# Sheet3.net
KiCad netlist of a schematic drawn in Altium Designer
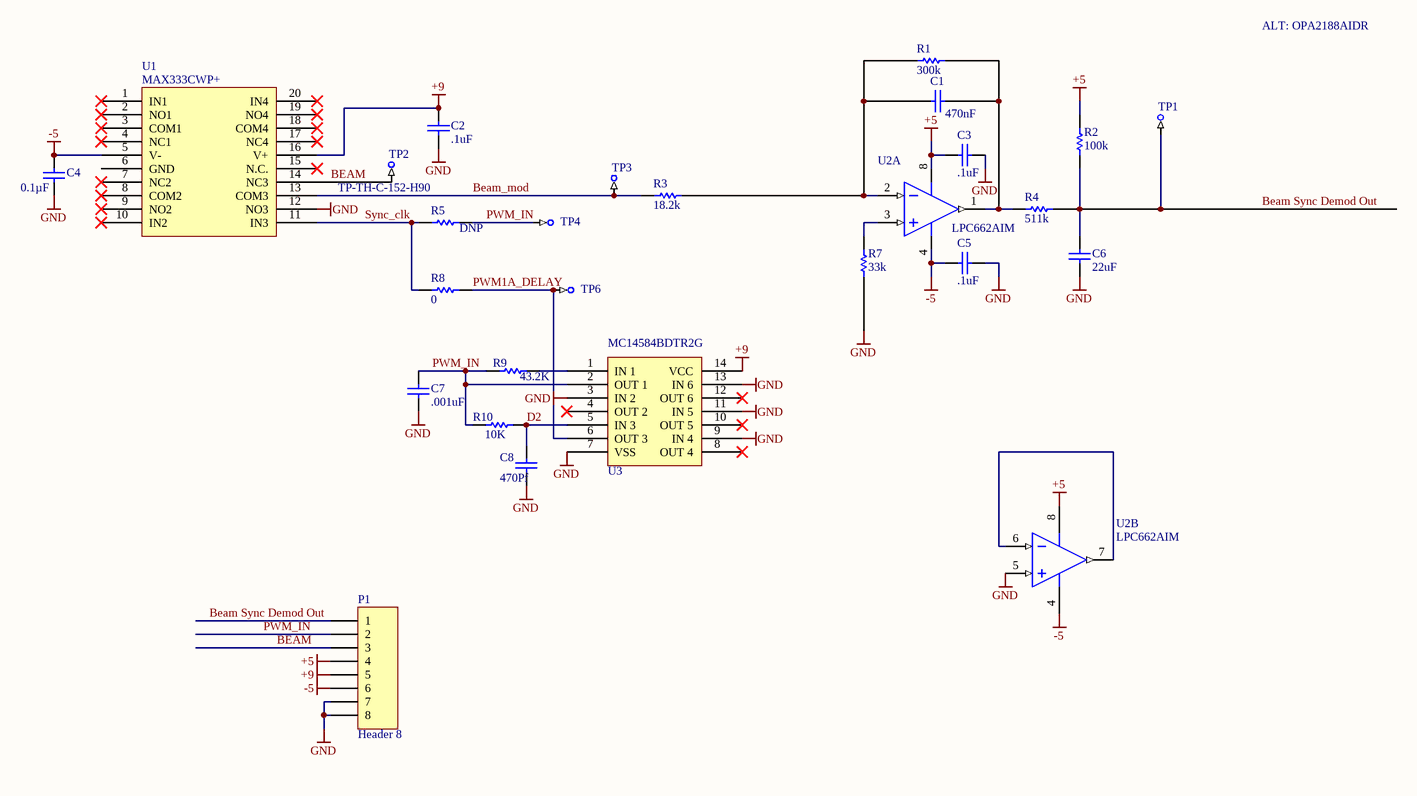
[diagram p0: Sheet3.SchDoc]

(export (version "E")
  (design (tool "Eeschema 10.0.6"))
  (components
    (comp (ref "C1")
      (value "470nF")
      (footprint "CAPC0805(2012)75_L")
      (description "CAP 150pF 16V ±10% 0805 (2012 Metric) Thickness 0.75mm SMD")
      (fields (field (name "TOLERANCE") "Â±10%"))
      (libsource (lib "Altium Content Vault") (part "CMP-1036-02117-1"))
    )
    (comp (ref "C2")
      (value ".1uF")
      (footprint "CAPC0805(2012)75_L")
      (description "CAP 150pF 16V ±10% 0805 (2012 Metric) Thickness 0.75mm SMD")
      (fields (field (name "TOLERANCE") "Â±10%"))
      (libsource (lib "Altium Content Vault") (part "CMP-1036-02117-1"))
    )
    (comp (ref "C3")
      (value ".1uF")
      (footprint "CAPC0805(2012)75_L")
      (description "CAP 150pF 16V ±10% 0805 (2012 Metric) Thickness 0.75mm SMD")
      (fields (field (name "TOLERANCE") "Â±10%"))
      (libsource (lib "Altium Content Vault") (part "CMP-1036-02117-1"))
    )
    (comp (ref "C4")
      (value "CAP CER 0.1UF 25V X7R 0805")
      (footprint "CAPC0805(2012)145_N")
      (fields
        (field (name "MANUFACTURER") "Murata Electronics North America")
        (field (name "MANUFACTURER PART NUMBER") "GRM21BR71E104KA01L")
        (field (name "CAPACITANCE") "0.1µF")
        (field (name "TOLERANCE") "±10%")
      )
      (libsource (lib "Altium Content Vault") (part "CMP-1036-04795-1"))
    )
    (comp (ref "C5")
      (value ".1uF")
      (footprint "CAPC0805(2012)75_L")
      (description "CAP 150pF 16V ±10% 0805 (2012 Metric) Thickness 0.75mm SMD")
      (fields (field (name "TOLERANCE") "Â±10%"))
      (libsource (lib "Altium Content Vault") (part "CMP-1036-02117-1"))
    )
    (comp (ref "C6")
      (value "22uF")
      (footprint "CAPC0805(2012)75_L")
      (description "CAP 150pF 16V ±10% 0805 (2012 Metric) Thickness 0.75mm SMD")
      (fields (field (name "TOLERANCE") "Â±10%"))
      (libsource (lib "Altium Content Vault") (part "CMP-1036-02117-1"))
    )
    (comp (ref "C7")
      (value ".001uF")
      (footprint "CAPC0805(2012)75_L")
      (description "CAP 150pF 16V ±10% 0805 (2012 Metric) Thickness 0.75mm SMD")
      (fields (field (name "TOLERANCE") "Â±10%"))
      (libsource (lib "Altium Content Vault") (part "CMP-1036-02117-1"))
    )
    (comp (ref "C8")
      (value "470Pf")
      (footprint "CAPC0805(2012)75_L")
      (description "CAP 150pF 16V ±10% 0805 (2012 Metric) Thickness 0.75mm SMD")
      (fields (field (name "TOLERANCE") "Â±10%"))
      (libsource (lib "Altium Content Vault") (part "CMP-1036-02117-1"))
    )
    (comp (ref "P1")
      (value "Header 8")
      (footprint "HDR1X8")
      (description "Header, 8-Pin")
      (fields (field (name "PUBLISHER") "Altium Limited"))
      (libsource (lib "Miscellaneous Connectors") (part "Header 8"))
    )
    (comp (ref "R1")
      (value "300k")
      (footprint "RESC0805(2012)_L")
      (description "2R55 0.125W 1% 0805 (2012 Metric)  SMD")
      (fields (field (name "TOLERANCE") "1 %") (field (name "POWER") "0.125 W"))
      (libsource (lib "Altium Content Vault") (part "CMP-1013-00215-1"))
    )
    (comp (ref "R2")
      (value "100k")
      (footprint "RESC0805(2012)_L")
      (description "2R55 0.125W 1% 0805 (2012 Metric)  SMD")
      (fields (field (name "TOLERANCE") "1 %") (field (name "POWER") "0.125 W"))
      (libsource (lib "Altium Content Vault") (part "CMP-1013-00215-1"))
    )
    (comp (ref "R3")
      (value "18.2k")
      (footprint "RESC0805(2012)_L")
      (description "2R55 0.125W 1% 0805 (2012 Metric)  SMD")
      (fields (field (name "TOLERANCE") "1 %") (field (name "POWER") "0.125 W"))
      (libsource (lib "Altium Content Vault") (part "CMP-1013-00215-1"))
    )
    (comp (ref "R4")
      (value "511k")
      (footprint "RESC0805(2012)_L")
      (description "2R55 0.125W 1% 0805 (2012 Metric)  SMD")
      (fields (field (name "TOLERANCE") "1 %") (field (name "POWER") "0.125 W"))
      (libsource (lib "Altium Content Vault") (part "CMP-1013-00215-1"))
    )
    (comp (ref "R5")
      (value "DNP")
      (footprint "RESC0805(2012)_L")
      (description "2R55 0.125W 1% 0805 (2012 Metric)  SMD")
      (fields (field (name "TOLERANCE") "1 %") (field (name "POWER") "0.125 W"))
      (libsource (lib "Altium Content Vault") (part "CMP-1013-00215-1"))
    )
    (comp (ref "R7")
      (value "33k")
      (footprint "RESC0805(2012)_L")
      (description "2R55 0.125W 1% 0805 (2012 Metric)  SMD")
      (fields (field (name "TOLERANCE") "1 %") (field (name "POWER") "0.125 W"))
      (libsource (lib "Altium Content Vault") (part "CMP-1013-00215-1"))
    )
    (comp (ref "R8")
      (value "0")
      (footprint "RESC0805(2012)_L")
      (description "2R55 0.125W 1% 0805 (2012 Metric)  SMD")
      (fields (field (name "TOLERANCE") "1 %") (field (name "POWER") "0.125 W"))
      (libsource (lib "Altium Content Vault") (part "CMP-1013-00215-1"))
    )
    (comp (ref "R9")
      (value "43.2K")
      (footprint "RESC0805(2012)_L")
      (description "2R55 0.125W 1% 0805 (2012 Metric)  SMD")
      (fields (field (name "TOLERANCE") "1 %") (field (name "POWER") "0.125 W"))
      (libsource (lib "Altium Content Vault") (part "CMP-1013-00215-1"))
    )
    (comp (ref "R10")
      (value "10K")
      (footprint "RESC0805(2012)_L")
      (description "2R55 0.125W 1% 0805 (2012 Metric)  SMD")
      (fields (field (name "TOLERANCE") "1 %") (field (name "POWER") "0.125 W"))
      (libsource (lib "Altium Content Vault") (part "CMP-1013-00215-1"))
    )
    (comp (ref "TP1")
      (value "TP-TH-C-152-H90")
      (footprint "TP-TH-C-152-H90")
      (description "Test Point, Through Hole, Hole Size 0.9 mm, PCB Mount with Silkscreen Box")
      (fields (field (name "MANUFACTURER") "No Vendor"))
      (libsource (lib "Altium Content Vault") (part "CMP-0484-00003-2"))
    )
    (comp (ref "TP2")
      (value "TP-TH-C-152-H90")
      (footprint "TP-TH-C-152-H90")
      (description "Test Point, Through Hole, Hole Size 0.9 mm, PCB Mount with Silkscreen Box")
      (fields (field (name "MANUFACTURER") "No Vendor"))
      (libsource (lib "Altium Content Vault") (part "TP-TH"))
    )
    (comp (ref "TP3")
      (value "TP-TH-C-152-H90")
      (footprint "TP-TH-C-152-H90")
      (description "Test Point, Through Hole, Hole Size 0.9 mm, PCB Mount with Silkscreen Box")
      (fields (field (name "MANUFACTURER") "No Vendor"))
      (libsource (lib "Altium Content Vault") (part "CMP-0484-00003-2"))
    )
    (comp (ref "TP4")
      (value "TP-TH-C-152-H90")
      (footprint "TP-TH-C-152-H90")
      (description "Test Point, Through Hole, Hole Size 0.9 mm, PCB Mount with Silkscreen Box")
      (fields (field (name "MANUFACTURER") "No Vendor"))
      (libsource (lib "Altium Content Vault") (part "CMP-0484-00003-2"))
    )
    (comp (ref "TP6")
      (value "TP-TH-C-152-H90")
      (footprint "TP-TH-C-152-H90")
      (description "Test Point, Through Hole, Hole Size 0.9 mm, PCB Mount with Silkscreen Box")
      (fields (field (name "MANUFACTURER") "No Vendor"))
      (libsource (lib "Altium Content Vault") (part "CMP-0484-00003-2"))
    )
    (comp (ref "U1")
      (value "MAX333CWP+")
      (footprint "TSOP65P640X90-20N")
      (description "IC SWITCH QUAD SPDT 20TSSOP")
      (fields (field (name "MANUFACTURER") "Maxim") (field (name "MANUFACTURER PART NUMBER") "MAX333AEUP+"))
      (libsource (lib "ZLS_Schematic_lib") (part "MAX333CWP+"))
    )
    (comp (ref "U2")
      (value "LPC662AIM")
      (footprint "D0008A_L")
      (description "Low Power CMOS Dual Operational Amplifier, 8-pin Narrow SOIC")
      (fields (field (name "MANUFACTURER") "Texas Instruments"))
      (libsource (lib "Altium Content Vault") (part "AMP-OPA-LM6132-8"))
    )
    (comp (ref "U3")
      (value "MC14584BDTR2G")
      (footprint "MC14584BDTR2G")
      (fields (field (name "MANUFACTURER") "ON Semiconductor") (field (name "BASE PART NUMBER") "4584"))
      (libsource (lib "ZLS_Schematic_lib") (part "MC14584BDTR2G"))
    )
  )
  (nets
    (net (code "1") (name "+5") (class "Default")
      (node (ref "C3") (pin "1") (pinfunction "1_1") (pintype "passive"))
      (node (ref "P1") (pin "4") (pinfunction "4_4") (pintype "passive"))
      (node (ref "R2") (pin "2") (pinfunction "2_2") (pintype "passive"))
      (node (ref "U2") (pin "8") (pinfunction "V+_8") (pintype "power_in"))
    )
    (net (code "2") (name "+9") (class "Default")
      (node (ref "C2") (pin "2") (pinfunction "2_2") (pintype "passive"))
      (node (ref "P1") (pin "5") (pinfunction "5_5") (pintype "passive"))
      (node (ref "U1") (pin "16") (pinfunction "V+_16") (pintype "power_in"))
      (node (ref "U3") (pin "14") (pinfunction "VCC_14") (pintype "passive"))
    )
    (net (code "3") (name "-5") (class "Default")
      (node (ref "C4") (pin "1") (pinfunction "1_1") (pintype "passive"))
      (node (ref "C5") (pin "1") (pinfunction "1_1") (pintype "passive"))
      (node (ref "P1") (pin "6") (pinfunction "6_6") (pintype "passive"))
      (node (ref "U1") (pin "5") (pinfunction "V-_5") (pintype "power_in"))
      (node (ref "U2") (pin "4") (pinfunction "V-_4") (pintype "power_in"))
    )
    (net (code "4") (name "/BEAM") (class "Default")
      (node (ref "P1") (pin "3") (pinfunction "3_3") (pintype "passive"))
      (node (ref "TP2") (pin "1") (pinfunction "1_1") (pintype "input"))
      (node (ref "U1") (pin "14") (pinfunction "NC3_14") (pintype "passive"))
    )
    (net (code "5") (name "/Beam Sync Demod Out") (class "Default")
      (node (ref "C6") (pin "2") (pinfunction "2_2") (pintype "passive"))
      (node (ref "P1") (pin "1") (pinfunction "1_1") (pintype "passive"))
      (node (ref "R2") (pin "1") (pinfunction "1_1") (pintype "passive"))
      (node (ref "R4") (pin "1") (pinfunction "1_1") (pintype "passive"))
      (node (ref "TP1") (pin "1") (pinfunction "1_1") (pintype "input"))
    )
    (net (code "6") (name "/Beam_mod") (class "Default")
      (node (ref "R3") (pin "2") (pinfunction "2_2") (pintype "passive"))
      (node (ref "TP3") (pin "1") (pinfunction "1_1") (pintype "input"))
      (node (ref "U1") (pin "13") (pinfunction "COM3_13") (pintype "passive"))
    )
    (net (code "7") (name "/D2") (class "Default")
      (node (ref "C8") (pin "2") (pinfunction "2_2") (pintype "passive"))
      (node (ref "R10") (pin "1") (pinfunction "1_1") (pintype "passive"))
      (node (ref "U3") (pin "5") (pinfunction "IN_3_5") (pintype "passive"))
    )
    (net (code "8") (name "/PWM1A_DELAY") (class "Default")
      (node (ref "R8") (pin "1") (pinfunction "1_1") (pintype "passive"))
      (node (ref "TP6") (pin "1") (pinfunction "1_1") (pintype "input"))
      (node (ref "U3") (pin "6") (pinfunction "OUT_3_6") (pintype "passive"))
    )
    (net (code "9") (name "/PWM_IN") (class "Default")
      (node (ref "C7") (pin "2") (pinfunction "2_2") (pintype "passive"))
      (node (ref "P1") (pin "2") (pinfunction "2_2") (pintype "passive"))
      (node (ref "R10") (pin "2") (pinfunction "2_2") (pintype "passive"))
      (node (ref "R5") (pin "1") (pinfunction "1_1") (pintype "passive"))
      (node (ref "R9") (pin "2") (pinfunction "2_2") (pintype "passive"))
      (node (ref "TP4") (pin "1") (pinfunction "1_1") (pintype "input"))
      (node (ref "U3") (pin "2") (pinfunction "OUT_1_2") (pintype "passive"))
    )
    (net (code "10") (name "/Sync_clk") (class "Default")
      (node (ref "R5") (pin "2") (pinfunction "2_2") (pintype "passive"))
      (node (ref "R8") (pin "2") (pinfunction "2_2") (pintype "passive"))
      (node (ref "U1") (pin "11") (pinfunction "IN3_11") (pintype "passive"))
    )
    (net (code "11") (name "GND") (class "Default")
      (node (ref "C2") (pin "1") (pinfunction "1_1") (pintype "passive"))
      (node (ref "C3") (pin "2") (pinfunction "2_2") (pintype "passive"))
      (node (ref "C4") (pin "2") (pinfunction "2_2") (pintype "passive"))
      (node (ref "C5") (pin "2") (pinfunction "2_2") (pintype "passive"))
      (node (ref "C6") (pin "1") (pinfunction "1_1") (pintype "passive"))
      (node (ref "C7") (pin "1") (pinfunction "1_1") (pintype "passive"))
      (node (ref "C8") (pin "1") (pinfunction "1_1") (pintype "passive"))
      (node (ref "P1") (pin "7") (pinfunction "7_7") (pintype "passive"))
      (node (ref "P1") (pin "8") (pinfunction "8_8") (pintype "passive"))
      (node (ref "R7") (pin "1") (pinfunction "1_1") (pintype "passive"))
      (node (ref "U1") (pin "12") (pinfunction "NO3_12") (pintype "passive"))
      (node (ref "U2") (pin "5") (pinfunction "INB+_5") (pintype "input"))
      (node (ref "U3") (pin "11") (pinfunction "IN_5_11") (pintype "passive"))
      (node (ref "U3") (pin "13") (pinfunction "IN_6_13") (pintype "passive"))
      (node (ref "U3") (pin "3") (pinfunction "IN_2_3") (pintype "passive"))
      (node (ref "U3") (pin "7") (pinfunction "VSS_7") (pintype "passive"))
      (node (ref "U3") (pin "9") (pinfunction "IN_4_9") (pintype "passive"))
    )
    (net (code "12") (name "Net-(U2A-INA+)") (class "Default")
      (node (ref "R7") (pin "2") (pinfunction "2_2") (pintype "passive"))
      (node (ref "U2") (pin "3") (pinfunction "INA+_3") (pintype "input"))
    )
    (net (code "13") (name "Net-(U2A-INA-)") (class "Default")
      (node (ref "C1") (pin "1") (pinfunction "1_1") (pintype "passive"))
      (node (ref "R1") (pin "2") (pinfunction "2_2") (pintype "passive"))
      (node (ref "R3") (pin "1") (pinfunction "1_1") (pintype "passive"))
      (node (ref "U2") (pin "2") (pinfunction "INA-_2") (pintype "input"))
    )
    (net (code "14") (name "Net-(U2A-OUTA)") (class "Default")
      (node (ref "C1") (pin "2") (pinfunction "2_2") (pintype "passive"))
      (node (ref "R1") (pin "1") (pinfunction "1_1") (pintype "passive"))
      (node (ref "R4") (pin "2") (pinfunction "2_2") (pintype "passive"))
      (node (ref "U2") (pin "1") (pinfunction "OUTA_1") (pintype "output"))
    )
    (net (code "15") (name "Net-(U2B-INB-)") (class "Default")
      (node (ref "U2") (pin "6") (pinfunction "INB-_6") (pintype "input"))
      (node (ref "U2") (pin "7") (pinfunction "OUTB_7") (pintype "output"))
    )
    (net (code "16") (name "Net-(U3-IN_1)") (class "Default")
      (node (ref "R9") (pin "1") (pinfunction "1_1") (pintype "passive"))
      (node (ref "U3") (pin "1") (pinfunction "IN_1_1") (pintype "passive"))
    )
    (net (code "17") (name "unconnected-(U1-COM1-Pad3)") (class "Default")
      (node (ref "U1") (pin "3") (pinfunction "COM1_3") (pintype "passive+no_connect"))
    )
    (net (code "18") (name "unconnected-(U1-COM2-Pad8)") (class "Default")
      (node (ref "U1") (pin "8") (pinfunction "COM2_8") (pintype "passive+no_connect"))
    )
    (net (code "19") (name "unconnected-(U1-COM4-Pad18)") (class "Default")
      (node (ref "U1") (pin "18") (pinfunction "COM4_18") (pintype "passive+no_connect"))
    )
    (net (code "20") (name "unconnected-(U1-GND-Pad6)") (class "Default")
      (node (ref "U1") (pin "6") (pinfunction "GND_6") (pintype "passive"))
    )
    (net (code "21") (name "unconnected-(U1-IN1-Pad1)") (class "Default")
      (node (ref "U1") (pin "1") (pinfunction "IN1_1") (pintype "passive+no_connect"))
    )
    (net (code "22") (name "unconnected-(U1-IN2-Pad10)") (class "Default")
      (node (ref "U1") (pin "10") (pinfunction "IN2_10") (pintype "passive+no_connect"))
    )
    (net (code "23") (name "unconnected-(U1-IN4-Pad20)") (class "Default")
      (node (ref "U1") (pin "20") (pinfunction "IN4_20") (pintype "passive+no_connect"))
    )
    (net (code "24") (name "unconnected-(U1-N.C.-Pad15)") (class "Default")
      (node (ref "U1") (pin "15") (pinfunction "N.C._15") (pintype "passive+no_connect"))
    )
    (net (code "25") (name "unconnected-(U1-NC1-Pad4)") (class "Default")
      (node (ref "U1") (pin "4") (pinfunction "NC1_4") (pintype "passive+no_connect"))
    )
    (net (code "26") (name "unconnected-(U1-NC2-Pad7)") (class "Default")
      (node (ref "U1") (pin "7") (pinfunction "NC2_7") (pintype "passive+no_connect"))
    )
    (net (code "27") (name "unconnected-(U1-NC4-Pad17)") (class "Default")
      (node (ref "U1") (pin "17") (pinfunction "NC4_17") (pintype "passive+no_connect"))
    )
    (net (code "28") (name "unconnected-(U1-NO1-Pad2)") (class "Default")
      (node (ref "U1") (pin "2") (pinfunction "NO1_2") (pintype "passive+no_connect"))
    )
    (net (code "29") (name "unconnected-(U1-NO2-Pad9)") (class "Default")
      (node (ref "U1") (pin "9") (pinfunction "NO2_9") (pintype "passive+no_connect"))
    )
    (net (code "30") (name "unconnected-(U1-NO4-Pad19)") (class "Default")
      (node (ref "U1") (pin "19") (pinfunction "NO4_19") (pintype "passive+no_connect"))
    )
    (net (code "31") (name "unconnected-(U3-OUT_2-Pad4)") (class "Default")
      (node (ref "U3") (pin "4") (pinfunction "OUT_2_4") (pintype "passive+no_connect"))
    )
    (net (code "32") (name "unconnected-(U3-OUT_4-Pad8)") (class "Default")
      (node (ref "U3") (pin "8") (pinfunction "OUT_4_8") (pintype "passive+no_connect"))
    )
    (net (code "33") (name "unconnected-(U3-OUT_5-Pad10)") (class "Default")
      (node (ref "U3") (pin "10") (pinfunction "OUT_5_10") (pintype "passive+no_connect"))
    )
    (net (code "34") (name "unconnected-(U3-OUT_6-Pad12)") (class "Default")
      (node (ref "U3") (pin "12") (pinfunction "OUT_6_12") (pintype "passive+no_connect"))
    )
  )
)
